# 8_5_WIFI_BT.net
KiCad netlist of a schematic drawn in Altium Designer
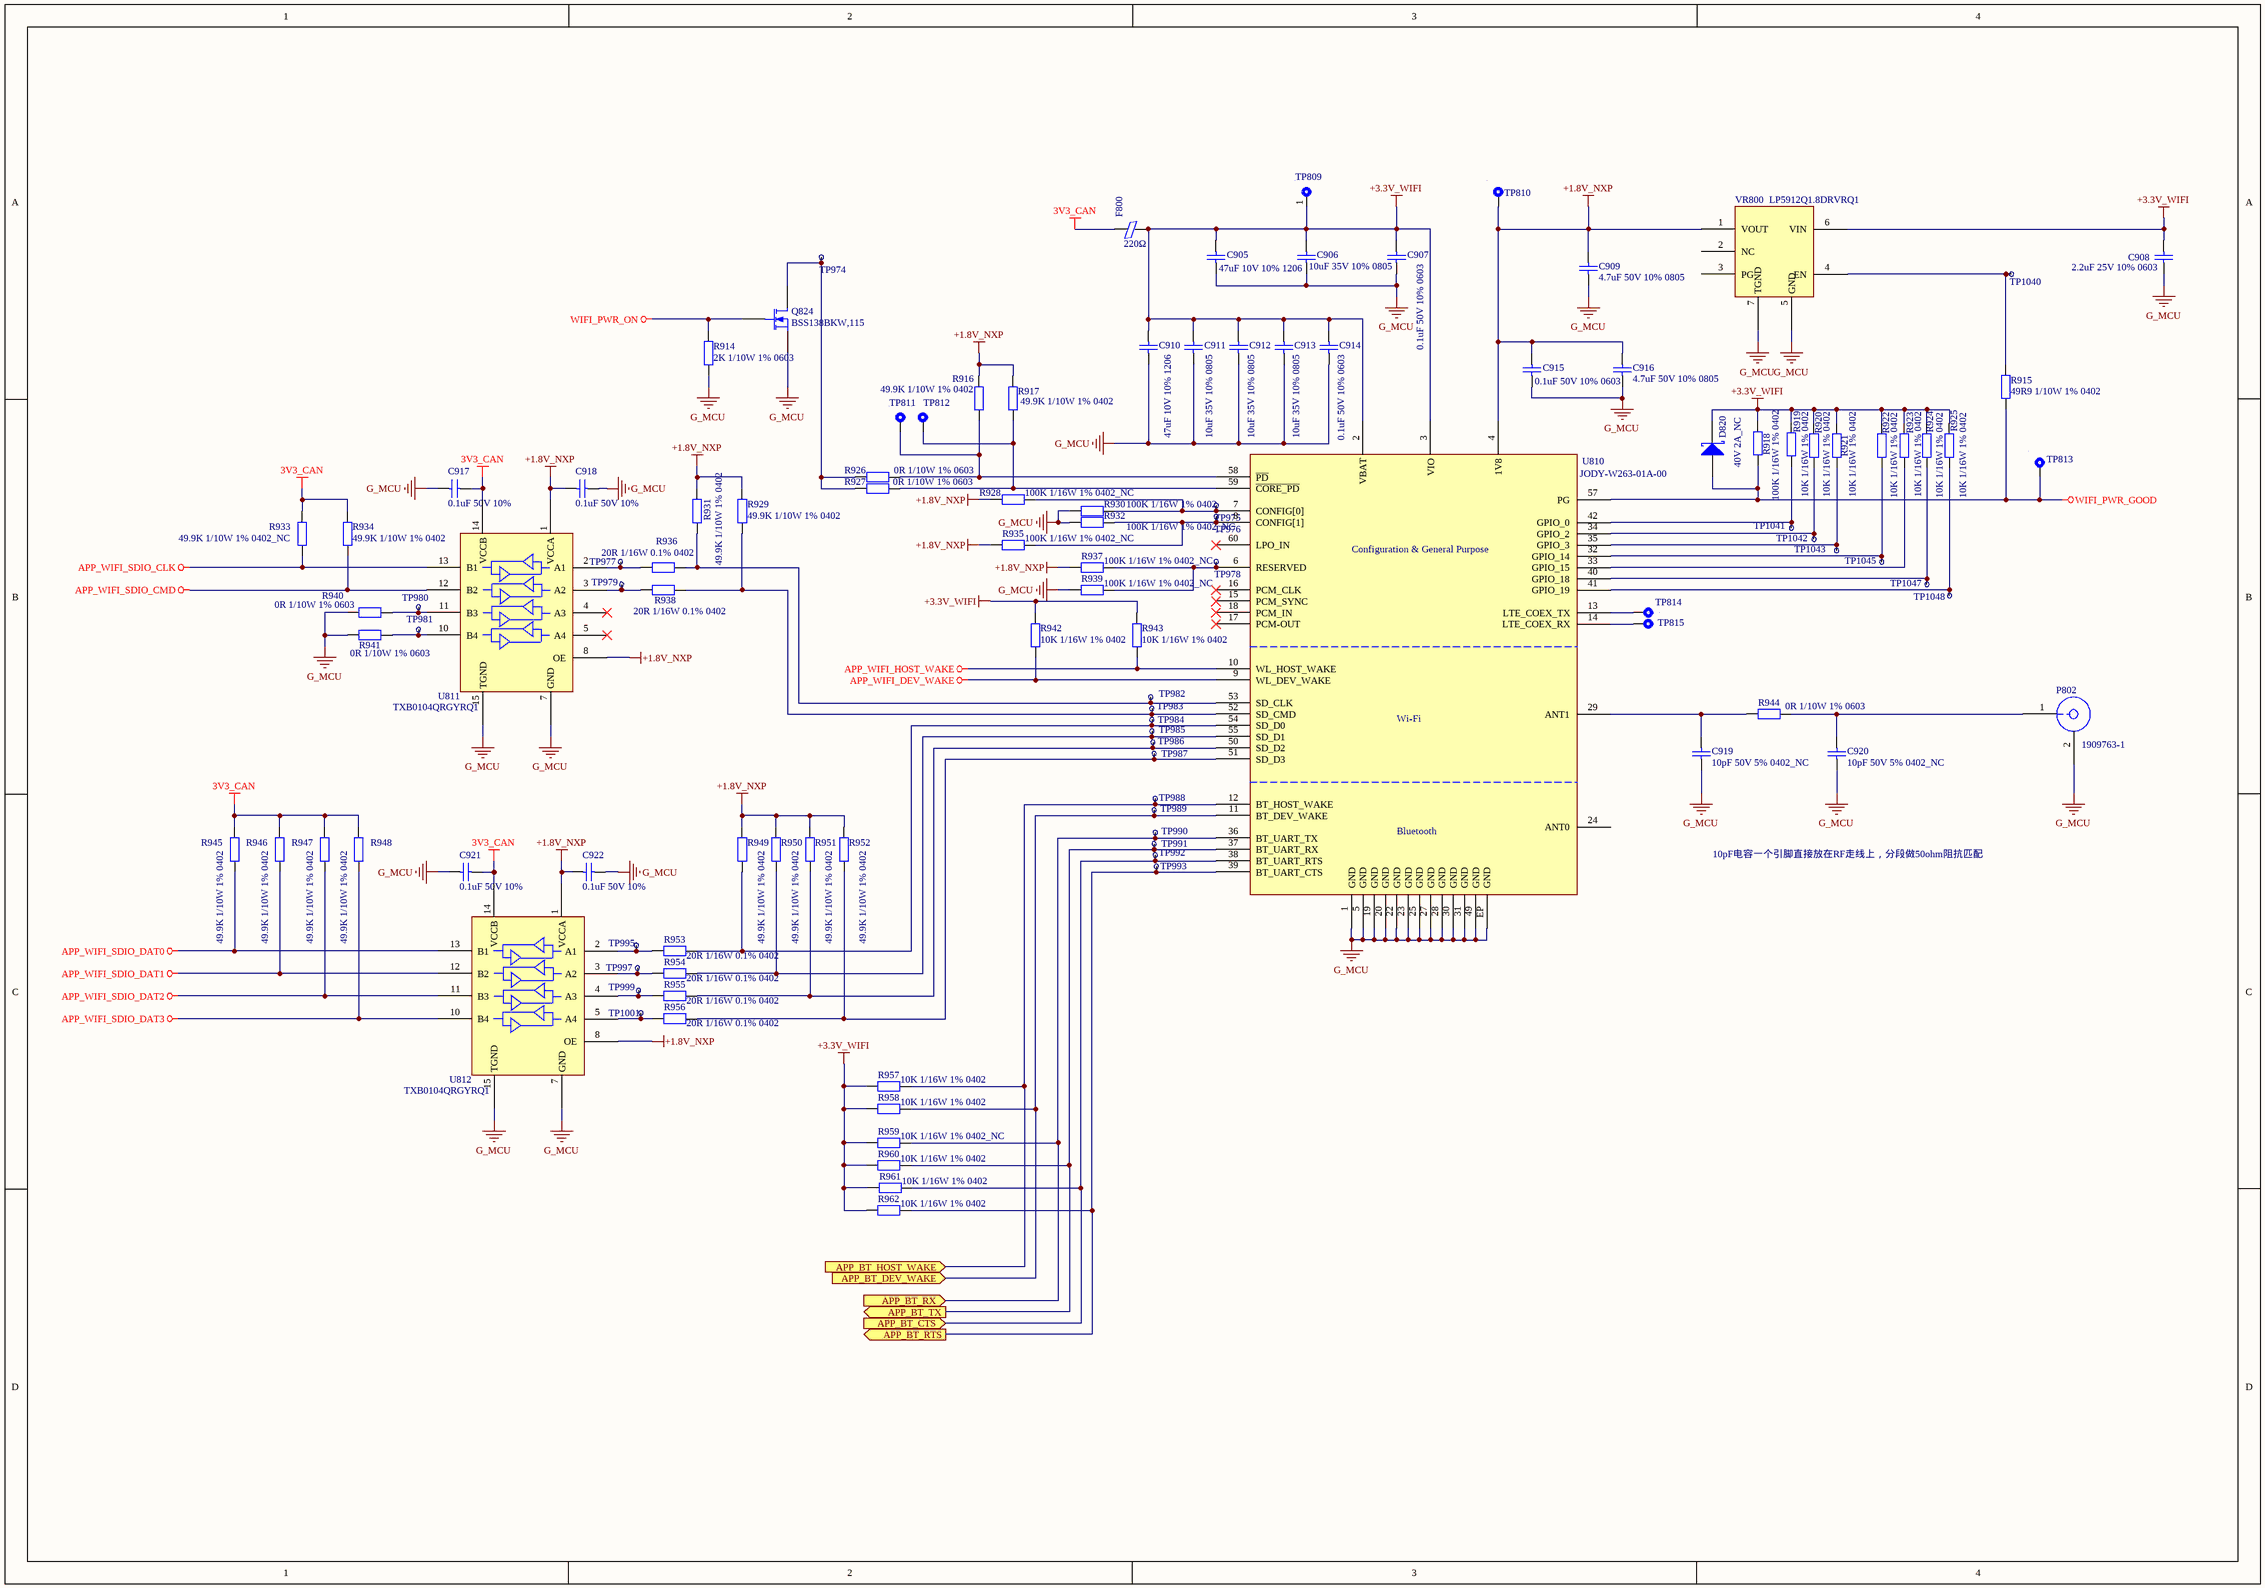
[diagram p0: 8.5 WIFI&BT.SchDoc]

(export (version "E")
  (design (tool "Eeschema 10.0.6"))
  (components
    (comp (ref "C905")
      (value "47uF 10V 10% 1206")
      (footprint "C1206")
      (description "CAP CER 47uF 10V 10% X5R 1206 SMD")
      (libsource (lib "Miscellaneous Devices") (part "Cap Semi"))
    )
    (comp (ref "C906")
      (value "10uF 35V 10% 0805")
      (footprint "C0805")
      (description "CAP CER 10uF 35V 10% X5R 0805 SMD")
      (libsource (lib "Miscellaneous Devices") (part "Cap Semi"))
    )
    (comp (ref "C907")
      (value "0.1uF 50V 10% 0603")
      (footprint "C0603")
      (description "CAP CER 0.1uF 50V 10% X7R 0603 SMD")
      (libsource (lib "Miscellaneous Devices") (part "Cap Semi"))
    )
    (comp (ref "C908")
      (value "2.2uF 25V 10% 0603")
      (footprint "C0603")
      (description "CAP CER 2.2uF 25V 10% X5R 0603 SMD")
      (libsource (lib "Miscellaneous Devices") (part "Cap Semi"))
    )
    (comp (ref "C909")
      (value "4.7uF 50V 10% 0805")
      (footprint "C0805")
      (description "CAP CER 4.7uF 50V 10% X7R 0805 SMD")
      (libsource (lib "Miscellaneous Devices") (part "Cap Semi"))
    )
    (comp (ref "C910")
      (value "47uF 10V 10% 1206")
      (footprint "C1206")
      (description "CAP CER 47uF 10V 10% X5R 1206 SMD")
      (libsource (lib "Miscellaneous Devices") (part "Cap Semi"))
    )
    (comp (ref "C911")
      (value "10uF 35V 10% 0805")
      (footprint "C0805")
      (description "CAP CER 10uF 35V 10% X5R 0805 SMD")
      (libsource (lib "Miscellaneous Devices") (part "Cap Semi"))
    )
    (comp (ref "C912")
      (value "10uF 35V 10% 0805")
      (footprint "C0805")
      (description "CAP CER 10uF 35V 10% X5R 0805 SMD")
      (libsource (lib "Miscellaneous Devices") (part "Cap Semi"))
    )
    (comp (ref "C913")
      (value "10uF 35V 10% 0805")
      (footprint "C0805")
      (description "CAP CER 10uF 35V 10% X5R 0805 SMD")
      (libsource (lib "Miscellaneous Devices") (part "Cap Semi"))
    )
    (comp (ref "C914")
      (value "0.1uF 50V 10% 0603")
      (footprint "C0603")
      (description "CAP CER 0.1uF 50V 10% X7R 0603 SMD")
      (libsource (lib "Miscellaneous Devices") (part "Cap Semi"))
    )
    (comp (ref "C915")
      (value "0.1uF 50V 10% 0603")
      (footprint "C0603")
      (description "CAP CER 0.1uF 50V 10% X7R 0603 SMD")
      (libsource (lib "Miscellaneous Devices") (part "Cap Semi"))
    )
    (comp (ref "C916")
      (value "4.7uF 50V 10% 0805")
      (footprint "C0805")
      (description "CAP CER 4.7uF 50V 10% X7R 0805 SMD")
      (libsource (lib "Miscellaneous Devices") (part "Cap Semi"))
    )
    (comp (ref "C917")
      (value "0.1uF 50V 10%")
      (footprint "C0603")
      (description "CAP CER 0.1uF 50V 10% X7R 0603 SMD")
      (libsource (lib "Miscellaneous Devices") (part "Cap"))
    )
    (comp (ref "C918")
      (value "0.1uF 50V 10%")
      (footprint "C0603")
      (description "CAP CER 0.1uF 50V 10% X7R 0603 SMD")
      (libsource (lib "Miscellaneous Devices") (part "Cap"))
    )
    (comp (ref "C919")
      (value "10pF 50V 5% 0402_NC")
      (footprint "C0402")
      (description "CAP CER 10pF 50V 5% C0G 0402 SMD")
      (libsource (lib "Miscellaneous Devices") (part "Cap Semi"))
    )
    (comp (ref "C920")
      (value "10pF 50V 5% 0402_NC")
      (footprint "C0402")
      (description "CAP CER 10pF 50V 5% C0G 0402 SMD")
      (libsource (lib "Miscellaneous Devices") (part "Cap Semi"))
    )
    (comp (ref "C921")
      (value "0.1uF 50V 10%")
      (footprint "C0603")
      (description "CAP CER 0.1uF 50V 10% X7R 0603 SMD")
      (libsource (lib "Miscellaneous Devices") (part "Cap"))
    )
    (comp (ref "C922")
      (value "0.1uF 50V 10%")
      (footprint "C0603")
      (description "CAP CER 0.1uF 50V 10% X7R 0603 SMD")
      (libsource (lib "Miscellaneous Devices") (part "Cap"))
    )
    (comp (ref "D820")
      (value "40V 2A_NC")
      (footprint "SOD123_FL")
      (description "SBD 40V 2A Vf=0.65V SOD-123 SMD")
      (libsource (lib "Miscellaneous Devices") (part "D Schottky"))
    )
    (comp (ref "F800")
      (value "220")
      (footprint "R0603")
      (fields (field (name "值") "220Ω"))
      (libsource (lib "电感磁珠类原理图封装库") (part "Ferrite Bead 220±25％Ω@100MHz 2.2A 0.05Ω F0603_0.95 BLM18KG221SH1D(Murata)"))
    )
    (comp (ref "P802")
      (value "1909763-1")
      (footprint "TE_1909763-1")
      (description "Connector, Receptacle, U.FL,  RF/Coaxial, Gold, 50 ohm Jack, DC-6GHZ")
      (libsource (lib "Connector") (part "Component_1"))
    )
    (comp (ref "Q824")
      (value "BSS138BKW,115")
      (footprint "SOT323")
      (description "MOSFET N-Channel 60V 320mA SOT-323")
      (libsource (lib "Miscellaneous Devices") (part "MOSFET-N"))
    )
    (comp (ref "R914")
      (value "2K 1/10W 1% 0603")
      (footprint "R0603")
      (description "RES Thick Film 2K 1/10W 1% 0603 SMD")
      (libsource (lib "") (part "Res2_3"))
    )
    (comp (ref "R915")
      (value "49R9 1/10W 1% 0402")
      (footprint "R0402")
      (description "RES Thick Film 49R9 1/10W 1% 0402 SMD")
      (libsource (lib "") (part "Res2_3"))
    )
    (comp (ref "R916")
      (value "49.9K 1/10W 1% 0402")
      (footprint "R0402")
      (description "RES Thick Film 49.9K 1/10W 1% 0402 SMD")
      (libsource (lib "") (part "Res2_1"))
    )
    (comp (ref "R917")
      (value "49.9K 1/10W 1% 0402")
      (footprint "R0402")
      (description "RES Thick Film 49.9K 1/10W 1% 0402 SMD")
      (libsource (lib "") (part "Res2_1"))
    )
    (comp (ref "R918")
      (value "100K 1/16W 1% 0402")
      (footprint "R0402")
      (description "RES Thick Film 100K 1/16W 1% 0402 SMD")
      (libsource (lib "") (part "Res2_3"))
    )
    (comp (ref "R919")
      (value "10K 1/16W 1% 0402")
      (footprint "R0402")
      (description "RES Thick Film 10K 1/16W 1% 0402 SMD")
      (libsource (lib "") (part "Res2_1"))
    )
    (comp (ref "R920")
      (value "10K 1/16W 1% 0402")
      (footprint "R0402")
      (description "RES Thick Film 10K 1/16W 1% 0402 SMD")
      (libsource (lib "") (part "Res2_1"))
    )
    (comp (ref "R921")
      (value "10K 1/16W 1% 0402")
      (footprint "R0402")
      (description "RES Thick Film 10K 1/16W 1% 0402 SMD")
      (libsource (lib "") (part "Res2_1"))
    )
    (comp (ref "R922")
      (value "10K 1/16W 1% 0402")
      (footprint "R0402")
      (description "RES Thick Film 10K 1/16W 1% 0402 SMD")
      (libsource (lib "") (part "Res2_1"))
    )
    (comp (ref "R923")
      (value "10K 1/16W 1% 0402")
      (footprint "R0402")
      (description "RES Thick Film 10K 1/16W 1% 0402 SMD")
      (libsource (lib "") (part "Res2_1"))
    )
    (comp (ref "R924")
      (value "10K 1/16W 1% 0402")
      (footprint "R0402")
      (description "RES Thick Film 10K 1/16W 1% 0402 SMD")
      (libsource (lib "") (part "Res2_1"))
    )
    (comp (ref "R925")
      (value "10K 1/16W 1% 0402")
      (footprint "R0402")
      (description "RES Thick Film 10K 1/16W 1% 0402 SMD")
      (libsource (lib "") (part "Res2_1"))
    )
    (comp (ref "R926")
      (value "0R 1/10W 1% 0603")
      (footprint "R0603")
      (description "RES Thick Film 0R 1/10W 1% 0603 AEC-Q200 HF SMD")
      (libsource (lib "Miscellaneous Devices") (part "Res2"))
    )
    (comp (ref "R927")
      (value "0R 1/10W 1% 0603")
      (footprint "R0603")
      (description "RES Thick Film 0R 1/10W 1% 0603 AEC-Q200 HF SMD")
      (libsource (lib "Miscellaneous Devices") (part "Res2"))
    )
    (comp (ref "R928")
      (value "100K 1/16W 1% 0402_NC")
      (footprint "R0402")
      (description "RES 100K 1/16W 1% 0402 SMD")
      (libsource (lib "Miscellaneous Devices") (part "Res2"))
    )
    (comp (ref "R929")
      (value "49.9K 1/10W 1% 0402")
      (footprint "R0402")
      (description "RES Thick Film 49.9K 1/10W 1% 0402 SMD")
      (libsource (lib "") (part "Res2_1"))
    )
    (comp (ref "R930")
      (value "100K 1/16W 1% 0402")
      (footprint "R0402")
      (description "RES 100K 1/16W 1% 0402 SMD")
      (libsource (lib "Miscellaneous Devices") (part "Res2"))
    )
    (comp (ref "R931")
      (value "49.9K 1/10W 1% 0402")
      (footprint "R0402")
      (description "RES Thick Film 49.9K 1/10W 1% 0402 SMD")
      (libsource (lib "") (part "Res2_1"))
    )
    (comp (ref "R932")
      (value "100K 1/16W 1% 0402_NC")
      (footprint "R0402")
      (description "RES 100K 1/16W 1% 0402 SMD")
      (libsource (lib "Miscellaneous Devices") (part "Res2"))
    )
    (comp (ref "R933")
      (value "49.9K 1/10W 1% 0402_NC")
      (footprint "R0402")
      (description "RES Thick Film 49.9K 1/10W 1% 0402 SMD")
      (libsource (lib "") (part "Res2_1"))
    )
    (comp (ref "R934")
      (value "49.9K 1/10W 1% 0402")
      (footprint "R0402")
      (description "RES Thick Film 49.9K 1/10W 1% 0402 SMD")
      (libsource (lib "") (part "Res2_1"))
    )
    (comp (ref "R935")
      (value "100K 1/16W 1% 0402_NC")
      (footprint "R0402")
      (description "RES 100K 1/16W 1% 0402 SMD")
      (libsource (lib "Miscellaneous Devices") (part "Res2"))
    )
    (comp (ref "R936")
      (value "20R 1/16W 0.1% 0402")
      (footprint "R0402")
      (description "RES 20R 1/16W 0.1% 0402 AEC-Q200 SMD")
      (libsource (lib "Miscellaneous Devices") (part "Res2"))
    )
    (comp (ref "R937")
      (value "100K 1/16W 1% 0402_NC")
      (footprint "R0402")
      (description "RES 100K 1/16W 1% 0402 SMD")
      (libsource (lib "Miscellaneous Devices") (part "Res2"))
    )
    (comp (ref "R938")
      (value "20R 1/16W 0.1% 0402")
      (footprint "R0402")
      (description "RES 20R 1/16W 0.1% 0402 AEC-Q200 SMD")
      (libsource (lib "Miscellaneous Devices") (part "Res2"))
    )
    (comp (ref "R939")
      (value "100K 1/16W 1% 0402_NC")
      (footprint "R0402")
      (description "RES 100K 1/16W 1% 0402 SMD")
      (libsource (lib "Miscellaneous Devices") (part "Res2"))
    )
    (comp (ref "R940")
      (value "0R 1/10W 1% 0603")
      (footprint "R0603")
      (description "RES Thick Film 0R 1/10W 1% 0603 AEC-Q200 HF SMD")
      (libsource (lib "Miscellaneous Devices") (part "Res2"))
    )
    (comp (ref "R941")
      (value "0R 1/10W 1% 0603")
      (footprint "R0603")
      (description "RES Thick Film 0R 1/10W 1% 0603 AEC-Q200 HF SMD")
      (libsource (lib "Miscellaneous Devices") (part "Res2"))
    )
    (comp (ref "R942")
      (value "10K 1/16W 1% 0402")
      (footprint "R0402")
      (description "RES Thick Film 10K 1/16W 1% 0402 SMD")
      (libsource (lib "") (part "Res2_1"))
    )
    (comp (ref "R943")
      (value "10K 1/16W 1% 0402")
      (footprint "R0402")
      (description "RES Thick Film 10K 1/16W 1% 0402 SMD")
      (libsource (lib "") (part "Res2_1"))
    )
    (comp (ref "R944")
      (value "0R 1/10W 1% 0603")
      (footprint "R0603")
      (description "RES Thick Film 0R 1/10W 1% 0603 SMD")
      (libsource (lib "") (part "Res2_2"))
    )
    (comp (ref "R945")
      (value "49.9K 1/10W 1% 0402")
      (footprint "R0402")
      (description "RES Thick Film 49.9K 1/10W 1% 0402 SMD")
      (libsource (lib "") (part "Res2_1"))
    )
    (comp (ref "R946")
      (value "49.9K 1/10W 1% 0402")
      (footprint "R0402")
      (description "RES Thick Film 49.9K 1/10W 1% 0402 SMD")
      (libsource (lib "") (part "Res2_1"))
    )
    (comp (ref "R947")
      (value "49.9K 1/10W 1% 0402")
      (footprint "R0402")
      (description "RES Thick Film 49.9K 1/10W 1% 0402 SMD")
      (libsource (lib "") (part "Res2_1"))
    )
    (comp (ref "R948")
      (value "49.9K 1/10W 1% 0402")
      (footprint "R0402")
      (description "RES Thick Film 49.9K 1/10W 1% 0402 SMD")
      (libsource (lib "") (part "Res2_1"))
    )
    (comp (ref "R949")
      (value "49.9K 1/10W 1% 0402")
      (footprint "R0402")
      (description "RES Thick Film 49.9K 1/10W 1% 0402 SMD")
      (libsource (lib "") (part "Res2_1"))
    )
    (comp (ref "R950")
      (value "49.9K 1/10W 1% 0402")
      (footprint "R0402")
      (description "RES Thick Film 49.9K 1/10W 1% 0402 SMD")
      (libsource (lib "") (part "Res2_1"))
    )
    (comp (ref "R951")
      (value "49.9K 1/10W 1% 0402")
      (footprint "R0402")
      (description "RES Thick Film 49.9K 1/10W 1% 0402 SMD")
      (libsource (lib "") (part "Res2_1"))
    )
    (comp (ref "R952")
      (value "49.9K 1/10W 1% 0402")
      (footprint "R0402")
      (description "RES Thick Film 49.9K 1/10W 1% 0402 SMD")
      (libsource (lib "") (part "Res2_1"))
    )
    (comp (ref "R953")
      (value "20R 1/16W 0.1% 0402")
      (footprint "R0402")
      (description "RES 20R 1/16W 0.1% 0402 AEC-Q200 SMD")
      (libsource (lib "Miscellaneous Devices") (part "Res2"))
    )
    (comp (ref "R954")
      (value "20R 1/16W 0.1% 0402")
      (footprint "R0402")
      (description "RES 20R 1/16W 0.1% 0402 AEC-Q200 SMD")
      (libsource (lib "Miscellaneous Devices") (part "Res2"))
    )
    (comp (ref "R955")
      (value "20R 1/16W 0.1% 0402")
      (footprint "R0402")
      (description "RES 20R 1/16W 0.1% 0402 AEC-Q200 SMD")
      (libsource (lib "Miscellaneous Devices") (part "Res2"))
    )
    (comp (ref "R956")
      (value "20R 1/16W 0.1% 0402")
      (footprint "R0402")
      (description "RES 20R 1/16W 0.1% 0402 AEC-Q200 SMD")
      (libsource (lib "Miscellaneous Devices") (part "Res2"))
    )
    (comp (ref "R957")
      (value "10K 1/16W 1% 0402")
      (footprint "R0402")
      (description "RES Thick Film 10K 1/16W 1% 0402 SMD")
      (libsource (lib "Miscellaneous Devices") (part "Res2"))
    )
    (comp (ref "R958")
      (value "10K 1/16W 1% 0402")
      (footprint "R0402")
      (description "RES Thick Film 10K 1/16W 1% 0402 SMD")
      (libsource (lib "Miscellaneous Devices") (part "Res2"))
    )
    (comp (ref "R959")
      (value "10K 1/16W 1% 0402_NC")
      (footprint "R0402")
      (description "RES Thick Film 10K 1/16W 1% 0402 SMD")
      (libsource (lib "Miscellaneous Devices") (part "Res2"))
    )
    (comp (ref "R960")
      (value "10K 1/16W 1% 0402")
      (footprint "R0402")
      (description "RES Thick Film 10K 1/16W 1% 0402 SMD")
      (libsource (lib "Miscellaneous Devices") (part "Res2"))
    )
    (comp (ref "R961")
      (value "10K 1/16W 1% 0402")
      (footprint "R0402")
      (description "RES Thick Film 10K 1/16W 1% 0402 SMD")
      (libsource (lib "Miscellaneous Devices") (part "Res2"))
    )
    (comp (ref "R962")
      (value "10K 1/16W 1% 0402")
      (footprint "R0402")
      (description "RES Thick Film 10K 1/16W 1% 0402 SMD")
      (libsource (lib "Miscellaneous Devices") (part "Res2"))
    )
    (comp (ref "TP809")
      (value "测试点")
      (footprint "测试点")
      (description "Test Point 1mm")
      (libsource (lib "") (part "Test Point_1"))
    )
    (comp (ref "TP810")
      (value "测试点")
      (footprint "测试点")
      (description "Test Point 1mm")
      (libsource (lib "Test Point") (part "Test Point"))
    )
    (comp (ref "TP811")
      (value "测试点")
      (footprint "测试点")
      (description "Test Point 1mm")
      (libsource (lib "Test Point") (part "Test Point"))
    )
    (comp (ref "TP812")
      (value "测试点")
      (footprint "测试点")
      (description "Test Point 1mm")
      (libsource (lib "Test Point") (part "Test Point"))
    )
    (comp (ref "TP813")
      (value "测试点")
      (footprint "测试点")
      (description "Test Point 1mm")
      (libsource (lib "Test Point") (part "Test Point"))
    )
    (comp (ref "TP814")
      (value "测试点")
      (footprint "测试点")
      (description "Test Point 1mm")
      (libsource (lib "Test Point") (part "Test Point"))
    )
    (comp (ref "TP815")
      (value "测试点")
      (footprint "测试点")
      (description "Test Point 1mm")
      (libsource (lib "Test Point") (part "Test Point"))
    )
    (comp (ref "TP974") (value "测试点") (footprint "测试点") (libsource (lib "原理图符号库2.0") (part "测试点")))
    (comp (ref "TP975") (value "测试点") (footprint "测试点") (libsource (lib "原理图符号库2.0") (part "测试点")))
    (comp (ref "TP976") (value "测试点") (footprint "测试点") (libsource (lib "原理图符号库2.0") (part "测试点")))
    (comp (ref "TP977") (value "测试点") (footprint "测试点") (libsource (lib "原理图符号库2.0") (part "测试点")))
    (comp (ref "TP978") (value "测试点") (footprint "测试点") (libsource (lib "原理图符号库2.0") (part "测试点")))
    (comp (ref "TP979") (value "测试点") (footprint "测试点") (libsource (lib "原理图符号库2.0") (part "测试点")))
    (comp (ref "TP980") (value "测试点") (footprint "测试点") (libsource (lib "原理图符号库2.0") (part "测试点")))
    (comp (ref "TP981") (value "测试点") (footprint "测试点") (libsource (lib "原理图符号库2.0") (part "测试点")))
    (comp (ref "TP982") (value "测试点") (footprint "测试点") (libsource (lib "原理图符号库2.0") (part "测试点")))
    (comp (ref "TP983") (value "测试点") (footprint "测试点") (libsource (lib "原理图符号库2.0") (part "测试点")))
    (comp (ref "TP984") (value "测试点") (footprint "测试点") (libsource (lib "原理图符号库2.0") (part "测试点")))
    (comp (ref "TP985") (value "测试点") (footprint "测试点") (libsource (lib "原理图符号库2.0") (part "测试点")))
    (comp (ref "TP986") (value "测试点") (footprint "测试点") (libsource (lib "原理图符号库2.0") (part "测试点")))
    (comp (ref "TP987") (value "测试点") (footprint "测试点") (libsource (lib "原理图符号库2.0") (part "测试点")))
    (comp (ref "TP988") (value "测试点") (footprint "测试点") (libsource (lib "原理图符号库2.0") (part "测试点")))
    (comp (ref "TP989") (value "测试点") (footprint "测试点") (libsource (lib "原理图符号库2.0") (part "测试点")))
    (comp (ref "TP990") (value "测试点") (footprint "测试点") (libsource (lib "原理图符号库2.0") (part "测试点")))
    (comp (ref "TP991") (value "测试点") (footprint "测试点") (libsource (lib "原理图符号库2.0") (part "测试点")))
    (comp (ref "TP992") (value "测试点") (footprint "测试点") (libsource (lib "原理图符号库2.0") (part "测试点")))
    (comp (ref "TP993") (value "测试点") (footprint "测试点") (libsource (lib "原理图符号库2.0") (part "测试点")))
    (comp (ref "TP995") (value "测试点") (footprint "测试点") (libsource (lib "原理图符号库2.0") (part "测试点")))
    (comp (ref "TP997") (value "测试点") (footprint "测试点") (libsource (lib "原理图符号库2.0") (part "测试点")))
    (comp (ref "TP999") (value "测试点") (footprint "测试点") (libsource (lib "原理图符号库2.0") (part "测试点")))
    (comp (ref "TP1001") (value "测试点") (footprint "测试点") (libsource (lib "原理图符号库2.0") (part "测试点")))
    (comp (ref "TP1040") (value "测试点") (footprint "测试点") (libsource (lib "原理图符号库2.0") (part "测试点")))
    (comp (ref "TP1041") (value "测试点") (footprint "测试点") (libsource (lib "原理图符号库2.0") (part "测试点")))
    (comp (ref "TP1042") (value "测试点") (footprint "测试点") (libsource (lib "原理图符号库2.0") (part "测试点")))
    (comp (ref "TP1043") (value "测试点") (footprint "测试点") (libsource (lib "原理图符号库2.0") (part "测试点")))
    (comp (ref "TP1045") (value "测试点") (footprint "测试点") (libsource (lib "原理图符号库2.0") (part "测试点")))
    (comp (ref "TP1047") (value "测试点") (footprint "测试点") (libsource (lib "原理图符号库2.0") (part "测试点")))
    (comp (ref "TP1048") (value "测试点") (footprint "测试点") (libsource (lib "原理图符号库2.0") (part "测试点")))
    (comp (ref "U810")
      (value "JODY-W263-01A-00")
      (footprint "UBLOX_JODY-W263")
      (description "IC, Serial-to-WIFI and Bluetooth Module, 2.4GHZ and 5GHZ, 802.11a/b/g/n/ac, Bluetooth 5.0")
      (libsource (lib "JODY-W263-01A-00") (part "JODY-W263-01A-00"))
    )
    (comp (ref "U811")
      (value "TXB0104QRGYRQ1")
      (footprint "TI_VQFN-14_RGY")
      (description "IC Voltage-Level Translator 4-Bit 1.2V~3.6V 1.65V~5.5V TI_VQFN-14-EP(3.5x3.5)")
      (libsource (lib "TXB0104QRGYRQ1") (part "TXB0104QRGYRQ1"))
    )
    (comp (ref "U812")
      (value "TXB0104QRGYRQ1")
      (footprint "TI_VQFN-14_RGY")
      (description "IC Voltage-Level Translator 4-Bit 1.2V~3.6V 1.65V~5.5V TI_VQFN-14-EP(3.5x3.5)")
      (libsource (lib "TXB0104QRGYRQ1") (part "TXB0104QRGYRQ1"))
    )
    (comp (ref "VR800")
      (value "LP5912Q1.8DRVRQ1")
      (footprint "TI_WSON-6_DRV")
      (description "IC LDO 6.5V 1.8V 500mA AEC-Q100 TI_WSON-6")
      (libsource (lib "LP5912Q1.8DRVRQ1") (part "LP5912Q1.8DRVRQ1"))
    )
  )
  (nets
    (net (code "1") (name "+1.8V_NXP") (class "Default")
      (node (ref "C909") (pin "2") (pinfunction "2_2") (pintype "passive"))
      (node (ref "C915") (pin "2") (pinfunction "2_2") (pintype "passive"))
      (node (ref "C916") (pin "2") (pinfunction "2_2") (pintype "passive"))
      (node (ref "C918") (pin "1") (pinfunction "1_1") (pintype "passive"))
      (node (ref "C922") (pin "1") (pinfunction "1_1") (pintype "passive"))
      (node (ref "R916") (pin "2") (pinfunction "2_2") (pintype "passive"))
      (node (ref "R917") (pin "2") (pinfunction "2_2") (pintype "passive"))
      (node (ref "R928") (pin "2") (pinfunction "2_2") (pintype "passive"))
      (node (ref "R929") (pin "2") (pinfunction "2_2") (pintype "passive"))
      (node (ref "R931") (pin "2") (pinfunction "2_2") (pintype "passive"))
      (node (ref "R935") (pin "2") (pinfunction "2_2") (pintype "passive"))
      (node (ref "R937") (pin "2") (pinfunction "2_2") (pintype "passive"))
      (node (ref "R949") (pin "2") (pinfunction "2_2") (pintype "passive"))
      (node (ref "R950") (pin "2") (pinfunction "2_2") (pintype "passive"))
      (node (ref "R951") (pin "2") (pinfunction "2_2") (pintype "passive"))
      (node (ref "R952") (pin "2") (pinfunction "2_2") (pintype "passive"))
      (node (ref "TP810") (pin "1") (pintype "passive"))
      (node (ref "U810") (pin "4") (pinfunction "1V8_4") (pintype "passive"))
      (node (ref "U811") (pin "1") (pinfunction "VCCA_1") (pintype "passive"))
      (node (ref "U811") (pin "8") (pinfunction "OE_8") (pintype "passive"))
      (node (ref "U812") (pin "1") (pinfunction "VCCA_1") (pintype "passive"))
      (node (ref "U812") (pin "8") (pinfunction "OE_8") (pintype "passive"))
      (node (ref "VR800") (pin "1") (pinfunction "VOUT_1") (pintype "passive"))
    )
    (net (code "2") (name "+3.3V_WIFI") (class "Default")
      (node (ref "C905") (pin "2") (pinfunction "2_2") (pintype "passive"))
      (node (ref "C906") (pin "2") (pinfunction "2_2") (pintype "passive"))
      (node (ref "C907") (pin "2") (pinfunction "2_2") (pintype "passive"))
      (node (ref "C908") (pin "2") (pinfunction "2_2") (pintype "passive"))
      (node (ref "C910") (pin "2") (pinfunction "2_2") (pintype "passive"))
      (node (ref "C911") (pin "2") (pinfunction "2_2") (pintype "passive"))
      (node (ref "C912") (pin "2") (pinfunction "2_2") (pintype "passive"))
      (node (ref "C913") (pin "2") (pinfunction "2_2") (pintype "passive"))
      (node (ref "C914") (pin "2") (pinfunction "2_2") (pintype "passive"))
      (node (ref "D820") (pin "K") (pinfunction "K_K") (pintype "passive"))
      (node (ref "F800") (pin "2") (pinfunction "2_2") (pintype "passive"))
      (node (ref "R918") (pin "1") (pinfunction "1_1") (pintype "passive"))
      (node (ref "R919") (pin "2") (pinfunction "2_2") (pintype "passive"))
      (node (ref "R920") (pin "2") (pinfunction "2_2") (pintype "passive"))
      (node (ref "R921") (pin "2") (pinfunction "2_2") (pintype "passive"))
      (node (ref "R922") (pin "2") (pinfunction "2_2") (pintype "passive"))
      (node (ref "R923") (pin "2") (pinfunction "2_2") (pintype "passive"))
      (node (ref "R924") (pin "2") (pinfunction "2_2") (pintype "passive"))
      (node (ref "R925") (pin "2") (pinfunction "2_2") (pintype "passive"))
      (node (ref "R942") (pin "2") (pinfunction "2_2") (pintype "passive"))
      (node (ref "R943") (pin "2") (pinfunction "2_2") (pintype "passive"))
      (node (ref "R957") (pin "2") (pinfunction "2_2") (pintype "passive"))
      (node (ref "R958") (pin "2") (pinfunction "2_2") (pintype "passive"))
      (node (ref "R959") (pin "2") (pinfunction "2_2") (pintype "passive"))
      (node (ref "R960") (pin "2") (pinfunction "2_2") (pintype "passive"))
      (node (ref "R961") (pin "2") (pinfunction "2_2") (pintype "passive"))
      (node (ref "R962") (pin "2") (pinfunction "2_2") (pintype "passive"))
      (node (ref "TP809") (pin "1") (pintype "passive"))
      (node (ref "U810") (pin "2") (pinfunction "VBAT_2") (pintype "passive"))
      (node (ref "U810") (pin "3") (pinfunction "VIO_3") (pintype "passive"))
      (node (ref "VR800") (pin "6") (pinfunction "VIN_6") (pintype "passive"))
    )
    (net (code "3") (name "/APP_BT_CTS") (class "Default")
      (node (ref "R961") (pin "1") (pinfunction "1_1") (pintype "passive"))
      (node (ref "TP992") (pin "1") (pinfunction "1_1") (pintype "passive"))
      (node (ref "U810") (pin "38") (pinfunction "BT_UART_RTS_38") (pintype "passive"))
    )
    (net (code "4") (name "/APP_BT_DEV_WAKE") (class "Default")
      (node (ref "R958") (pin "1") (pinfunction "1_1") (pintype "passive"))
      (node (ref "TP989") (pin "1") (pinfunction "1_1") (pintype "passive"))
      (node (ref "U810") (pin "11") (pinfunction "BT_DEV_WAKE_11") (pintype "passive"))
    )
    (net (code "5") (name "/APP_BT_HOST_WAKE") (class "Default")
      (node (ref "R957") (pin "1") (pinfunction "1_1") (pintype "passive"))
      (node (ref "TP988") (pin "1") (pinfunction "1_1") (pintype "passive"))
      (node (ref "U810") (pin "12") (pinfunction "BT_HOST_WAKE_12") (pintype "passive"))
    )
    (net (code "6") (name "/APP_BT_RTS") (class "Default")
      (node (ref "R962") (pin "1") (pinfunction "1_1") (pintype "passive"))
      (node (ref "TP993") (pin "1") (pinfunction "1_1") (pintype "passive"))
      (node (ref "U810") (pin "39") (pinfunction "BT_UART_CTS_39") (pintype "passive"))
    )
    (net (code "7") (name "/APP_BT_RX") (class "Default")
      (node (ref "R959") (pin "1") (pinfunction "1_1") (pintype "passive"))
      (node (ref "TP990") (pin "1") (pinfunction "1_1") (pintype "passive"))
      (node (ref "U810") (pin "36") (pinfunction "BT_UART_TX_36") (pintype "passive"))
    )
    (net (code "8") (name "/APP_BT_TX") (class "Default")
      (node (ref "R960") (pin "1") (pinfunction "1_1") (pintype "passive"))
      (node (ref "TP991") (pin "1") (pinfunction "1_1") (pintype "passive"))
      (node (ref "U810") (pin "37") (pinfunction "BT_UART_RX_37") (pintype "passive"))
    )
    (net (code "9") (name "3V3_CAN") (class "Default")
      (node (ref "C917") (pin "2") (pinfunction "2_2") (pintype "passive"))
      (node (ref "C921") (pin "2") (pinfunction "2_2") (pintype "passive"))
      (node (ref "F800") (pin "1") (pinfunction "1_1") (pintype "passive"))
      (node (ref "R933") (pin "2") (pinfunction "2_2") (pintype "passive"))
      (node (ref "R934") (pin "2") (pinfunction "2_2") (pintype "passive"))
      (node (ref "R945") (pin "2") (pinfunction "2_2") (pintype "passive"))
      (node (ref "R946") (pin "2") (pinfunction "2_2") (pintype "passive"))
      (node (ref "R947") (pin "2") (pinfunction "2_2") (pintype "passive"))
      (node (ref "R948") (pin "2") (pinfunction "2_2") (pintype "passive"))
      (node (ref "U811") (pin "14") (pinfunction "VCCB_14") (pintype "passive"))
      (node (ref "U812") (pin "14") (pinfunction "VCCB_14") (pintype "passive"))
    )
    (net (code "10") (name "APP_WIFI_DEV_WAKE") (class "Default")
      (node (ref "R942") (pin "1") (pinfunction "1_1") (pintype "passive"))
      (node (ref "U810") (pin "9") (pinfunction "WL_DEV_WAKE_9") (pintype "passive"))
    )
    (net (code "11") (name "APP_WIFI_HOST_WAKE") (class "Default")
      (node (ref "R943") (pin "1") (pinfunction "1_1") (pintype "passive"))
      (node (ref "U810") (pin "10") (pinfunction "WL_HOST_WAKE_10") (pintype "passive"))
    )
    (net (code "12") (name "APP_WIFI_SDIO_CLK") (class "Default")
      (node (ref "R933") (pin "1") (pinfunction "1_1") (pintype "passive"))
      (node (ref "U811") (pin "13") (pinfunction "B1_13") (pintype "passive"))
    )
    (net (code "13") (name "APP_WIFI_SDIO_CMD") (class "Default")
      (node (ref "R934") (pin "1") (pinfunction "1_1") (pintype "passive"))
      (node (ref "U811") (pin "12") (pinfunction "B2_12") (pintype "passive"))
    )
    (net (code "14") (name "APP_WIFI_SDIO_DAT0") (class "Default")
      (node (ref "R945") (pin "1") (pinfunction "1_1") (pintype "passive"))
      (node (ref "U812") (pin "13") (pinfunction "B1_13") (pintype "passive"))
    )
    (net (code "15") (name "APP_WIFI_SDIO_DAT1") (class "Default")
      (node (ref "R946") (pin "1") (pinfunction "1_1") (pintype "passive"))
      (node (ref "U812") (pin "12") (pinfunction "B2_12") (pintype "passive"))
    )
    (net (code "16") (name "APP_WIFI_SDIO_DAT2") (class "Default")
      (node (ref "R947") (pin "1") (pinfunction "1_1") (pintype "passive"))
      (node (ref "U812") (pin "11") (pinfunction "B3_11") (pintype "passive"))
    )
    (net (code "17") (name "APP_WIFI_SDIO_DAT3") (class "Default")
      (node (ref "R948") (pin "1") (pinfunction "1_1") (pintype "passive"))
      (node (ref "U812") (pin "10") (pinfunction "B4_10") (pintype "passive"))
    )
    (net (code "18") (name "G_MCU") (class "Default")
      (node (ref "C905") (pin "1") (pinfunction "1_1") (pintype "passive"))
      (node (ref "C906") (pin "1") (pinfunction "1_1") (pintype "passive"))
      (node (ref "C907") (pin "1") (pinfunction "1_1") (pintype "passive"))
      (node (ref "C908") (pin "1") (pinfunction "1_1") (pintype "passive"))
      (node (ref "C909") (pin "1") (pinfunction "1_1") (pintype "passive"))
      (node (ref "C910") (pin "1") (pinfunction "1_1") (pintype "passive"))
      (node (ref "C911") (pin "1") (pinfunction "1_1") (pintype "passive"))
      (node (ref "C912") (pin "1") (pinfunction "1_1") (pintype "passive"))
      (node (ref "C913") (pin "1") (pinfunction "1_1") (pintype "passive"))
      (node (ref "C914") (pin "1") (pinfunction "1_1") (pintype "passive"))
      (node (ref "C915") (pin "1") (pinfunction "1_1") (pintype "passive"))
      (node (ref "C916") (pin "1") (pinfunction "1_1") (pintype "passive"))
      (node (ref "C917") (pin "1") (pinfunction "1_1") (pintype "passive"))
      (node (ref "C918") (pin "2") (pinfunction "2_2") (pintype "passive"))
      (node (ref "C919") (pin "1") (pinfunction "1_1") (pintype "passive"))
      (node (ref "C920") (pin "1") (pinfunction "1_1") (pintype "passive"))
      (node (ref "C921") (pin "1") (pinfunction "1_1") (pintype "passive"))
      (node (ref "C922") (pin "2") (pinfunction "2_2") (pintype "passive"))
      (node (ref "P802") (pin "2") (pintype "passive"))
      (node (ref "Q824") (pin "S") (pinfunction "S_S") (pintype "passive"))
      (node (ref "R914") (pin "2") (pinfunction "2_2") (pintype "passive"))
      (node (ref "R930") (pin "2") (pinfunction "2_2") (pintype "passive"))
      (node (ref "R932") (pin "2") (pinfunction "2_2") (pintype "passive"))
      (node (ref "R939") (pin "2") (pinfunction "2_2") (pintype "passive"))
      (node (ref "R940") (pin "2") (pinfunction "2_2") (pintype "passive"))
      (node (ref "R941") (pin "2") (pinfunction "2_2") (pintype "passive"))
      (node (ref "U810") (pin "1") (pinfunction "GND_1") (pintype "passive"))
      (node (ref "U810") (pin "19") (pinfunction "GND_19") (pintype "passive"))
      (node (ref "U810") (pin "20") (pinfunction "GND_20") (pintype "passive"))
      (node (ref "U810") (pin "22") (pinfunction "GND_22") (pintype "passive"))
      (node (ref "U810") (pin "23") (pinfunction "GND_23") (pintype "passive"))
      (node (ref "U810") (pin "25") (pinfunction "GND_25") (pintype "passive"))
      (node (ref "U810") (pin "27") (pinfunction "GND_27") (pintype "passive"))
      (node (ref "U810") (pin "28") (pinfunction "GND_28") (pintype "passive"))
      (node (ref "U810") (pin "30") (pinfunction "GND_30") (pintype "passive"))
      (node (ref "U810") (pin "31") (pinfunction "GND_31") (pintype "passive"))
      (node (ref "U810") (pin "49") (pinfunction "GND_49") (pintype "passive"))
      (node (ref "U810") (pin "5") (pinfunction "GND_5") (pintype "passive"))
      (node (ref "U810") (pin "EP") (pinfunction "GND_EP") (pintype "passive"))
      (node (ref "U811") (pin "15") (pinfunction "TGND_15") (pintype "passive"))
      (node (ref "U811") (pin "7") (pinfunction "GND_7") (pintype "passive"))
      (node (ref "U812") (pin "15") (pinfunction "TGND_15") (pintype "passive"))
      (node (ref "U812") (pin "7") (pinfunction "GND_7") (pintype "passive"))
      (node (ref "VR800") (pin "5") (pinfunction "GND_5") (pintype "passive"))
      (node (ref "VR800") (pin "7") (pinfunction "TGND_7") (pintype "passive"))
    )
    (net (code "19") (name "Net-(C920-Pad2)") (class "Default")
      (node (ref "C920") (pin "2") (pinfunction "2_2") (pintype "passive"))
      (node (ref "P802") (pin "1") (pintype "passive"))
      (node (ref "R944") (pin "2") (pinfunction "2_2") (pintype "passive"))
    )
    (net (code "20") (name "Net-(Q824-PadD)") (class "Default")
      (node (ref "Q824") (pin "D") (pinfunction "D_D") (pintype "passive"))
      (node (ref "R926") (pin "2") (pinfunction "2_2") (pintype "passive"))
      (node (ref "R927") (pin "2") (pinfunction "2_2") (pintype "passive"))
      (node (ref "TP974") (pin "1") (pinfunction "1_1") (pintype "passive"))
    )
    (net (code "21") (name "Net-(U810-ANT1)") (class "Default")
      (node (ref "C919") (pin "2") (pinfunction "2_2") (pintype "passive"))
      (node (ref "R944") (pin "1") (pinfunction "1_1") (pintype "passive"))
      (node (ref "U810") (pin "29") (pinfunction "ANT1_29") (pintype "passive"))
    )
    (net (code "22") (name "Net-(U810-CONFIG[0])") (class "Default")
      (node (ref "R928") (pin "1") (pinfunction "1_1") (pintype "passive"))
      (node (ref "R930") (pin "1") (pinfunction "1_1") (pintype "passive"))
      (node (ref "TP975") (pin "1") (pinfunction "1_1") (pintype "passive"))
      (node (ref "U810") (pin "7") (pinfunction "CONFIG[0]_7") (pintype "passive"))
    )
    (net (code "23") (name "Net-(U810-CONFIG[1])") (class "Default")
      (node (ref "R932") (pin "1") (pinfunction "1_1") (pintype "passive"))
      (node (ref "R935") (pin "1") (pinfunction "1_1") (pintype "passive"))
      (node (ref "TP976") (pin "1") (pinfunction "1_1") (pintype "passive"))
      (node (ref "U810") (pin "8") (pinfunction "CONFIG[1]_8") (pintype "passive"))
    )
    (net (code "24") (name "Net-(U810-GPIO_0)") (class "Default")
      (node (ref "R919") (pin "1") (pinfunction "1_1") (pintype "passive"))
      (node (ref "TP1041") (pin "1") (pinfunction "1_1") (pintype "passive"))
      (node (ref "U810") (pin "42") (pinfunction "GPIO_0_42") (pintype "passive"))
    )
    (net (code "25") (name "Net-(U810-GPIO_2)") (class "Default")
      (node (ref "R920") (pin "1") (pinfunction "1_1") (pintype "passive"))
      (node (ref "TP1042") (pin "1") (pinfunction "1_1") (pintype "passive"))
      (node (ref "U810") (pin "34") (pinfunction "GPIO_2_34") (pintype "passive"))
    )
    (net (code "26") (name "Net-(U810-GPIO_3)") (class "Default")
      (node (ref "R921") (pin "1") (pinfunction "1_1") (pintype "passive"))
      (node (ref "TP1043") (pin "1") (pinfunction "1_1") (pintype "passive"))
      (node (ref "U810") (pin "35") (pinfunction "GPIO_3_35") (pintype "passive"))
    )
    (net (code "27") (name "Net-(U810-GPIO_14)") (class "Default")
      (node (ref "R922") (pin "1") (pinfunction "1_1") (pintype "passive"))
      (node (ref "TP1045") (pin "1") (pinfunction "1_1") (pintype "passive"))
      (node (ref "U810") (pin "32") (pinfunction "GPIO_14_32") (pintype "passive"))
    )
    (net (code "28") (name "Net-(U810-GPIO_15)") (class "Default")
      (node (ref "R923") (pin "1") (pinfunction "1_1") (pintype "passive"))
      (node (ref "U810") (pin "33") (pinfunction "GPIO_15_33") (pintype "passive"))
    )
    (net (code "29") (name "Net-(U810-GPIO_18)") (class "Default")
      (node (ref "R924") (pin "1") (pinfunction "1_1") (pintype "passive"))
      (node (ref "TP1047") (pin "1") (pinfunction "1_1") (pintype "passive"))
      (node (ref "U810") (pin "40") (pinfunction "GPIO_18_40") (pintype "passive"))
    )
    (net (code "30") (name "Net-(U810-GPIO_19)") (class "Default")
      (node (ref "R925") (pin "1") (pinfunction "1_1") (pintype "passive"))
      (node (ref "TP1048") (pin "1") (pinfunction "1_1") (pintype "passive"))
      (node (ref "U810") (pin "41") (pinfunction "GPIO_19_41") (pintype "passive"))
    )
    (net (code "31") (name "Net-(U810-LTE_COEX_RX)") (class "Default")
      (node (ref "TP815") (pin "1") (pintype "passive"))
      (node (ref "U810") (pin "14") (pinfunction "LTE_COEX_RX_14") (pintype "passive"))
    )
    (net (code "32") (name "Net-(U810-LTE_COEX_TX)") (class "Default")
      (node (ref "TP814") (pin "1") (pintype "passive"))
      (node (ref "U810") (pin "13") (pinfunction "LTE_COEX_TX_13") (pintype "passive"))
    )
    (net (code "33") (name "Net-(U810-RESERVED)") (class "Default")
      (node (ref "R937") (pin "1") (pinfunction "1_1") (pintype "passive"))
      (node (ref "R939") (pin "1") (pinfunction "1_1") (pintype "passive"))
      (node (ref "TP978") (pin "1") (pinfunction "1_1") (pintype "passive"))
      (node (ref "U810") (pin "6") (pinfunction "RESERVED_6") (pintype "passive"))
    )
    (net (code "34") (name "Net-(U810-SD_CLK)") (class "Default")
      (node (ref "R931") (pin "1") (pinfunction "1_1") (pintype "passive"))
      (node (ref "R936") (pin "1") (pinfunction "1_1") (pintype "passive"))
      (node (ref "TP982") (pin "1") (pinfunction "1_1") (pintype "passive"))
      (node (ref "U810") (pin "53") (pinfunction "SD_CLK_53") (pintype "passive"))
    )
    (net (code "35") (name "Net-(U810-SD_CMD)") (class "Default")
      (node (ref "R929") (pin "1") (pinfunction "1_1") (pintype "passive"))
      (node (ref "R938") (pin "1") (pinfunction "1_1") (pintype "passive"))
      (node (ref "TP983") (pin "1") (pinfunction "1_1") (pintype "passive"))
      (node (ref "U810") (pin "52") (pinfunction "SD_CMD_52") (pintype "passive"))
    )
    (net (code "36") (name "Net-(U810-SD_D0)") (class "Default")
      (node (ref "R949") (pin "1") (pinfunction "1_1") (pintype "passive"))
      (node (ref "R953") (pin "1") (pinfunction "1_1") (pintype "passive"))
      (node (ref "TP984") (pin "1") (pinfunction "1_1") (pintype "passive"))
      (node (ref "U810") (pin "54") (pinfunction "SD_D0_54") (pintype "passive"))
    )
    (net (code "37") (name "Net-(U810-SD_D1)") (class "Default")
      (node (ref "R950") (pin "1") (pinfunction "1_1") (pintype "passive"))
      (node (ref "R954") (pin "1") (pinfunction "1_1") (pintype "passive"))
      (node (ref "TP985") (pin "1") (pinfunction "1_1") (pintype "passive"))
      (node (ref "U810") (pin "55") (pinfunction "SD_D1_55") (pintype "passive"))
    )
    (net (code "38") (name "Net-(U810-SD_D2)") (class "Default")
      (node (ref "R951") (pin "1") (pinfunction "1_1") (pintype "passive"))
      (node (ref "R955") (pin "1") (pinfunction "1_1") (pintype "passive"))
      (node (ref "TP986") (pin "1") (pinfunction "1_1") (pintype "passive"))
      (node (ref "U810") (pin "50") (pinfunction "SD_D2_50") (pintype "passive"))
    )
    (net (code "39") (name "Net-(U810-SD_D3)") (class "Default")
      (node (ref "R952") (pin "1") (pinfunction "1_1") (pintype "passive"))
      (node (ref "R956") (pin "1") (pinfunction "1_1") (pintype "passive"))
      (node (ref "TP987") (pin "1") (pinfunction "1_1") (pintype "passive"))
      (node (ref "U810") (pin "51") (pinfunction "SD_D3_51") (pintype "passive"))
    )
    (net (code "40") (name "Net-(U810-~{CORE_PD})") (class "Default")
      (node (ref "R917") (pin "1") (pinfunction "1_1") (pintype "passive"))
      (node (ref "R927") (pin "1") (pinfunction "1_1") (pintype "passive"))
      (node (ref "TP812") (pin "1") (pintype "passive"))
      (node (ref "U810") (pin "59") (pinfunction "~{CORE_PD}_59") (pintype "passive"))
    )
    (net (code "41") (name "Net-(U810-~{PD})") (class "Default")
      (node (ref "R916") (pin "1") (pinfunction "1_1") (pintype "passive"))
      (node (ref "R926") (pin "1") (pinfunction "1_1") (pintype "passive"))
      (node (ref "TP811") (pin "1") (pintype "passive"))
      (node (ref "U810") (pin "58") (pinfunction "~{PD}_58") (pintype "passive"))
    )
    (net (code "42") (name "Net-(U811-A1)") (class "Default")
      (node (ref "R936") (pin "2") (pinfunction "2_2") (pintype "passive"))
      (node (ref "TP977") (pin "1") (pinfunction "1_1") (pintype "passive"))
      (node (ref "U811") (pin "2") (pinfunction "A1_2") (pintype "passive"))
    )
    (net (code "43") (name "Net-(U811-A2)") (class "Default")
      (node (ref "R938") (pin "2") (pinfunction "2_2") (pintype "passive"))
      (node (ref "TP979") (pin "1") (pinfunction "1_1") (pintype "passive"))
      (node (ref "U811") (pin "3") (pinfunction "A2_3") (pintype "passive"))
    )
    (net (code "44") (name "Net-(U811-B3)") (class "Default")
      (node (ref "R940") (pin "1") (pinfunction "1_1") (pintype "passive"))
      (node (ref "TP980") (pin "1") (pinfunction "1_1") (pintype "passive"))
      (node (ref "U811") (pin "11") (pinfunction "B3_11") (pintype "passive"))
    )
    (net (code "45") (name "Net-(U811-B4)") (class "Default")
      (node (ref "R941") (pin "1") (pinfunction "1_1") (pintype "passive"))
      (node (ref "TP981") (pin "1") (pinfunction "1_1") (pintype "passive"))
      (node (ref "U811") (pin "10") (pinfunction "B4_10") (pintype "passive"))
    )
    (net (code "46") (name "Net-(U812-A1)") (class "Default")
      (node (ref "R953") (pin "2") (pinfunction "2_2") (pintype "passive"))
      (node (ref "TP995") (pin "1") (pinfunction "1_1") (pintype "passive"))
      (node (ref "U812") (pin "2") (pinfunction "A1_2") (pintype "passive"))
    )
    (net (code "47") (name "Net-(U812-A2)") (class "Default")
      (node (ref "R954") (pin "2") (pinfunction "2_2") (pintype "passive"))
      (node (ref "TP997") (pin "1") (pinfunction "1_1") (pintype "passive"))
      (node (ref "U812") (pin "3") (pinfunction "A2_3") (pintype "passive"))
    )
    (net (code "48") (name "Net-(U812-A3)") (class "Default")
      (node (ref "R955") (pin "2") (pinfunction "2_2") (pintype "passive"))
      (node (ref "TP999") (pin "1") (pinfunction "1_1") (pintype "passive"))
      (node (ref "U812") (pin "4") (pinfunction "A3_4") (pintype "passive"))
    )
    (net (code "49") (name "Net-(U812-A4)") (class "Default")
      (node (ref "R956") (pin "2") (pinfunction "2_2") (pintype "passive"))
      (node (ref "TP1001") (pin "1") (pinfunction "1_1") (pintype "passive"))
      (node (ref "U812") (pin "5") (pinfunction "A4_5") (pintype "passive"))
    )
    (net (code "50") (name "Net-(VR800-EN)") (class "Default")
      (node (ref "R915") (pin "1") (pinfunction "1_1") (pintype "passive"))
      (node (ref "TP1040") (pin "1") (pinfunction "1_1") (pintype "passive"))
      (node (ref "VR800") (pin "4") (pinfunction "EN_4") (pintype "passive"))
    )
    (net (code "51") (name "WIFI_PWR_GOOD") (class "Default")
      (node (ref "D820") (pin "A") (pinfunction "A_A") (pintype "passive"))
      (node (ref "R915") (pin "2") (pinfunction "2_2") (pintype "passive"))
      (node (ref "R918") (pin "2") (pinfunction "2_2") (pintype "passive"))
      (node (ref "TP813") (pin "1") (pintype "passive"))
      (node (ref "U810") (pin "57") (pinfunction "PG_57") (pintype "passive"))
    )
    (net (code "52") (name "WIFI_PWR_ON") (class "Default")
      (node (ref "Q824") (pin "G") (pinfunction "G_G") (pintype "passive"))
      (node (ref "R914") (pin "1") (pinfunction "1_1") (pintype "passive"))
    )
    (net (code "53") (name "unconnected-(U810-ANT0-Pad24)") (class "Default")
      (node (ref "U810") (pin "24") (pinfunction "ANT0_24") (pintype "passive"))
    )
    (net (code "54") (name "unconnected-(U810-LPO_IN-Pad60)") (class "Default")
      (node (ref "U810") (pin "60") (pinfunction "LPO_IN_60") (pintype "passive+no_connect"))
    )
    (net (code "55") (name "unconnected-(U810-PCM-OUT-Pad17)") (class "Default")
      (node (ref "U810") (pin "17") (pinfunction "PCM-OUT_17") (pintype "passive+no_connect"))
    )
    (net (code "56") (name "unconnected-(U810-PCM_CLK-Pad16)") (class "Default")
      (node (ref "U810") (pin "16") (pinfunction "PCM_CLK_16") (pintype "passive+no_connect"))
    )
    (net (code "57") (name "unconnected-(U810-PCM_IN-Pad18)") (class "Default")
      (node (ref "U810") (pin "18") (pinfunction "PCM_IN_18") (pintype "passive+no_connect"))
    )
    (net (code "58") (name "unconnected-(U810-PCM_SYNC-Pad15)") (class "Default")
      (node (ref "U810") (pin "15") (pinfunction "PCM_SYNC_15") (pintype "passive+no_connect"))
    )
    (net (code "59") (name "unconnected-(U811-A3-Pad4)") (class "Default")
      (node (ref "U811") (pin "4") (pinfunction "A3_4") (pintype "passive+no_connect"))
    )
    (net (code "60") (name "unconnected-(U811-A4-Pad5)") (class "Default")
      (node (ref "U811") (pin "5") (pinfunction "A4_5") (pintype "passive+no_connect"))
    )
    (net (code "61") (name "unconnected-(VR800-NC-Pad2)") (class "Default")
      (node (ref "VR800") (pin "2") (pinfunction "NC_2") (pintype "passive"))
    )
    (net (code "62") (name "unconnected-(VR800-PG-Pad3)") (class "Default")
      (node (ref "VR800") (pin "3") (pinfunction "PG_3") (pintype "passive"))
    )
  )
)
